# Py_car_2021-03-04.net
KiCad netlist of a schematic drawn in EasyEDA
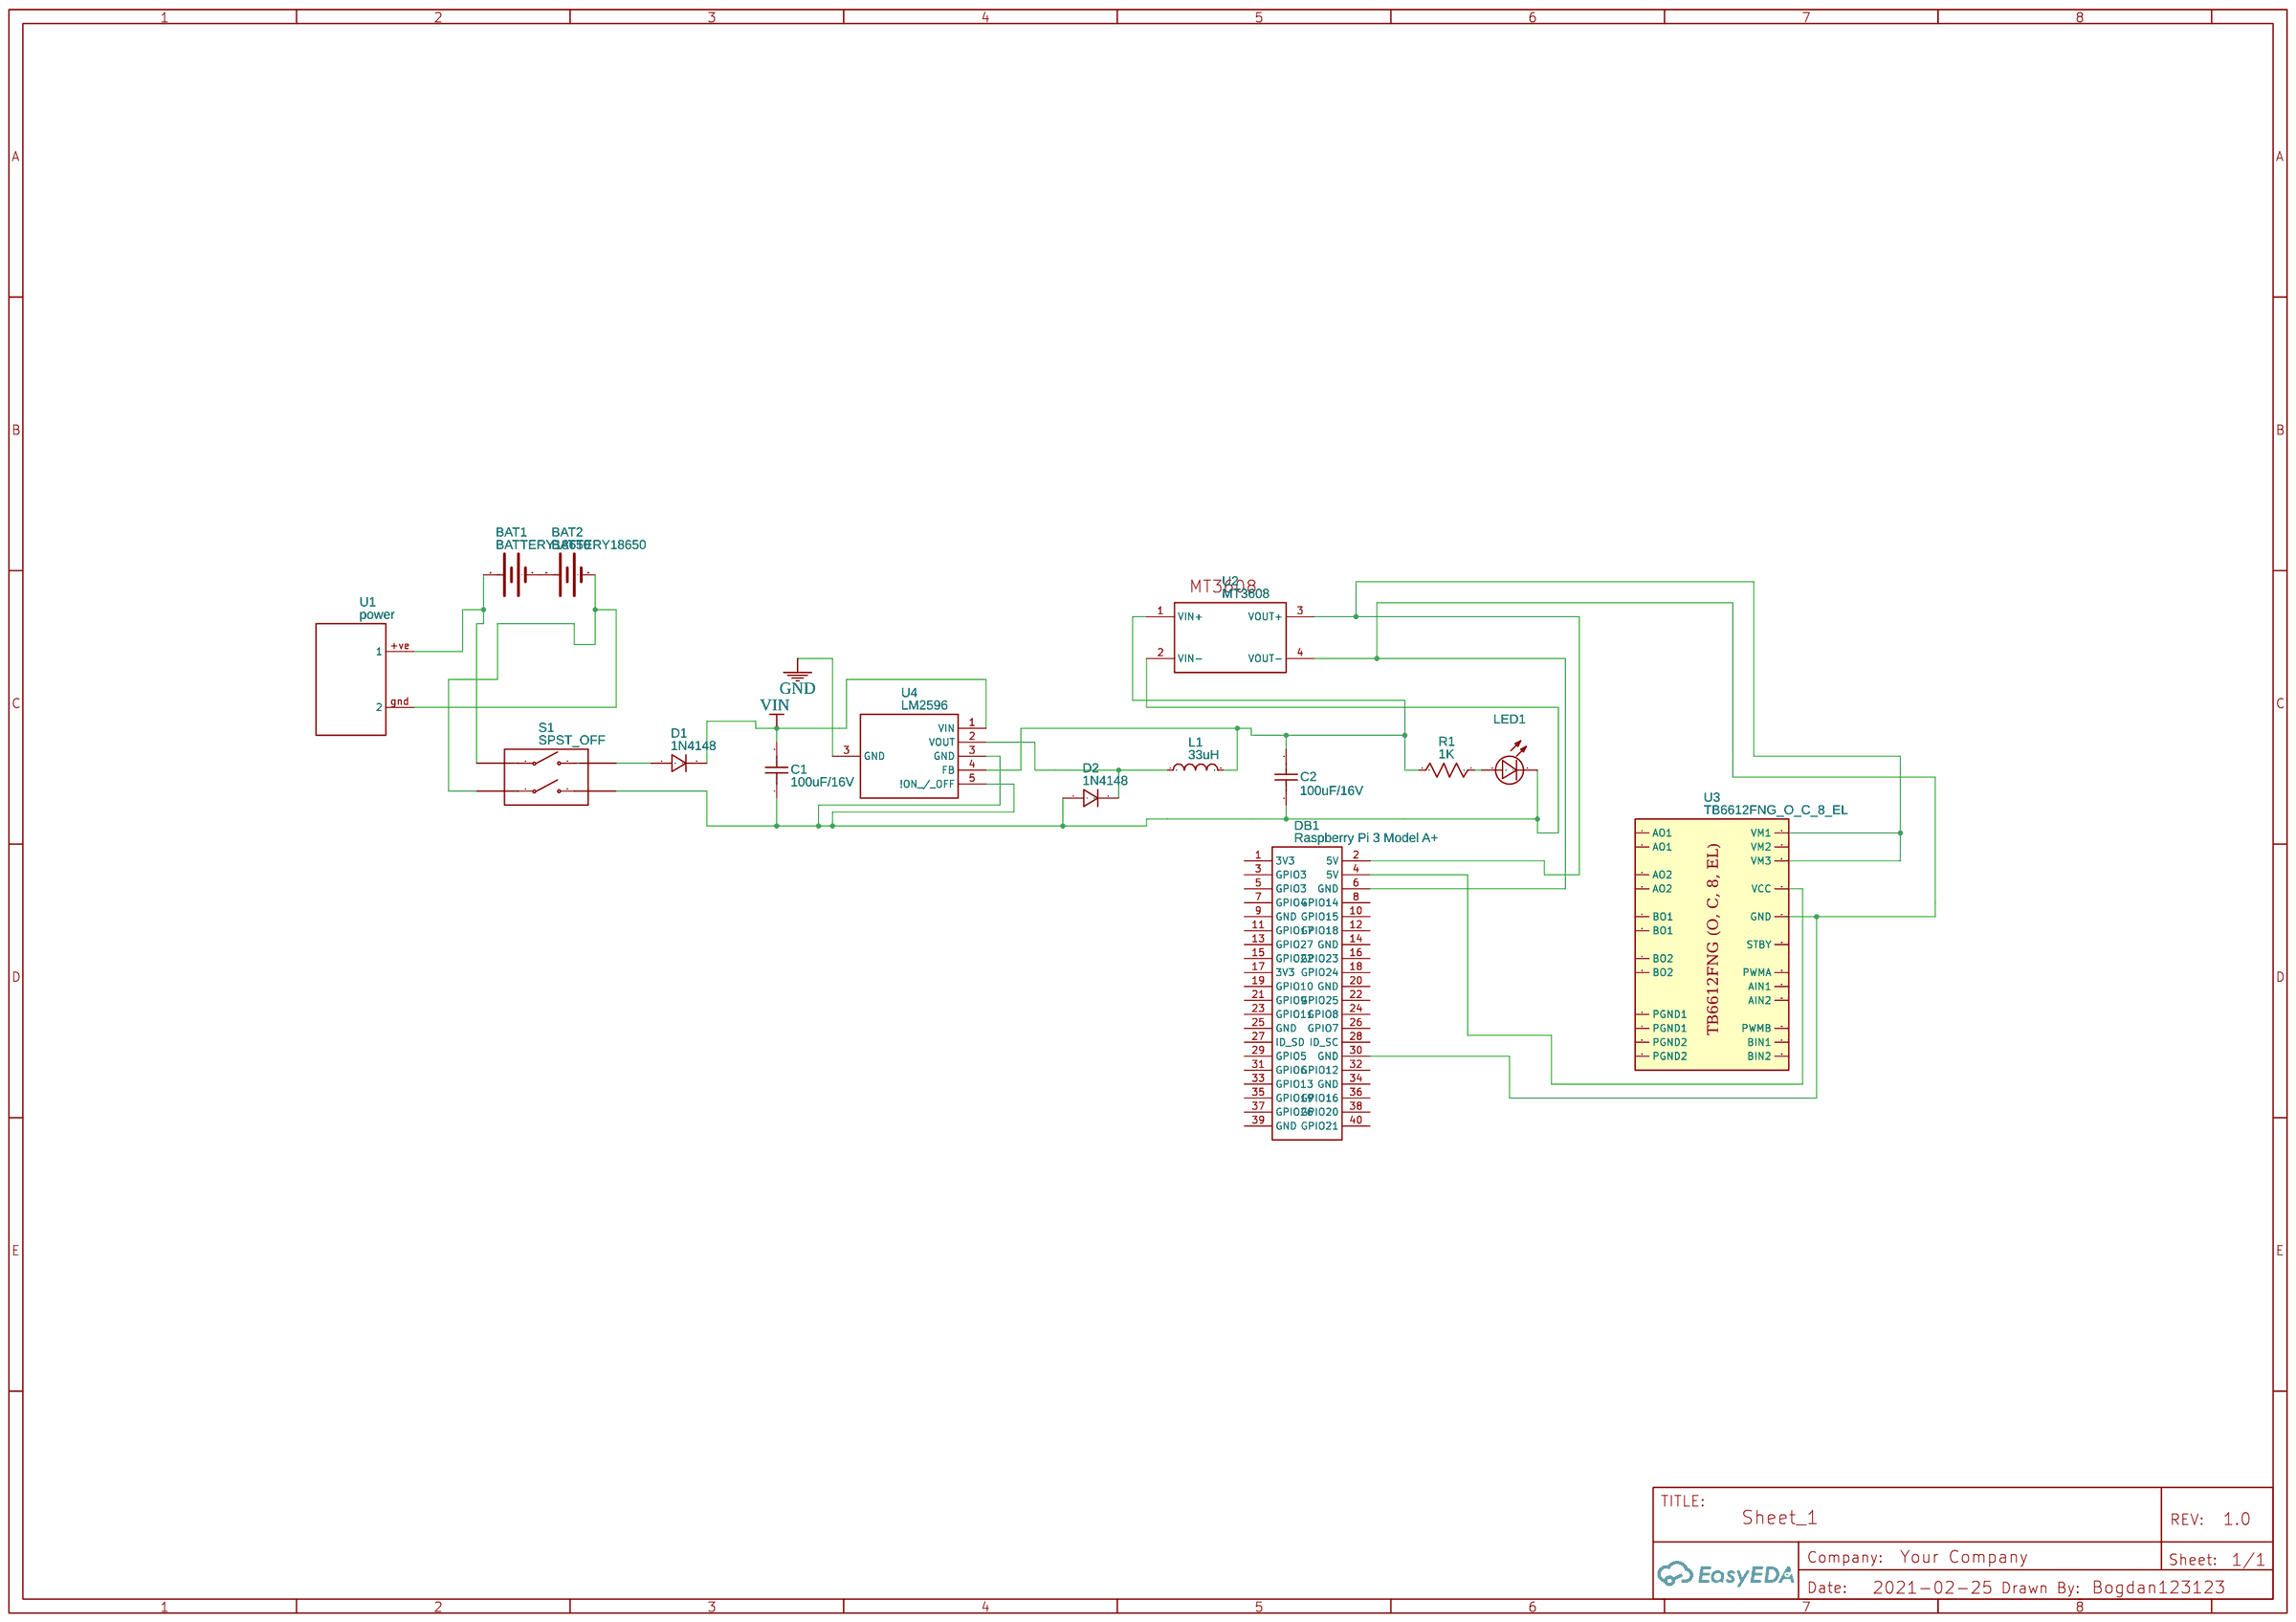
[diagram p0: schematic sheet]

(export (version "E")
  (design (tool "Eeschema 10.0.6"))
  (components
    (comp (ref "BAT1") (value "BATTERY18650") (libsource (lib "") (part "BATTERY18650")))
    (comp (ref "BAT2") (value "BATTERY18650") (libsource (lib "") (part "BATTERY18650")))
    (comp (ref "C1") (value "100uF/16V") (libsource (lib "") (part "Capacitor_US")))
    (comp (ref "C2") (value "100uF/16V") (libsource (lib "") (part "Capacitor_US")))
    (comp (ref "D1") (value "1N4148") (libsource (lib "") (part "1N4148")))
    (comp (ref "D2") (value "1N4148") (libsource (lib "") (part "1N4148")))
    (comp (ref "DB1")
      (value "Raspberry Pi 3 Model A+")
      (fields
        (field (name "BOM_Manufacturer Part") "RPI3-MODAP")
        (field (name "BOM_Supplier Part") "2946269")
      )
      (libsource (lib "") (part "Raspberry Pi 3 Model A+"))
    )
    (comp (ref "L1") (value "33uH") (libsource (lib "") (part "Inductor")))
    (comp (ref "LED1") (value "LED") (libsource (lib "") (part "LED")))
    (comp (ref "R1") (value "1K") (libsource (lib "") (part "Resistor_US")))
    (comp (ref "S1") (value "SPST_OFF") (libsource (lib "") (part "SPST_OFF")))
    (comp (ref "U1") (value "power") (libsource (lib "") (part "power")))
    (comp (ref "U2") (value "MT3608") (libsource (lib "") (part "MT3608")))
    (comp (ref "U3") (value "TB6612FNG_O_C_8_EL") (libsource (lib "") (part "TB6612FNG_O_C_8_EL")))
    (comp (ref "U4") (value "LM2596") (libsource (lib "") (part "LM2596")))
  )
  (nets
    (net (code "1") (name "GND") (class "Default")
      (node (ref "U4") (pin "3") (pinfunction "GND_3") (pintype "unspecified"))
    )
    (net (code "2") (name "Net-(BAT1-+)") (class "Default")
      (node (ref "BAT1") (pin "PWR@1") (pinfunction "+_PWR@1") (pintype "passive"))
      (node (ref "U1") (pin "+ve") (pinfunction "1_+ve") (pintype "unspecified"))
    )
    (net (code "3") (name "Net-(BAT1--)") (class "Default")
      (node (ref "BAT1") (pin "GND@1") (pinfunction "-_GND@1") (pintype "passive"))
      (node (ref "BAT2") (pin "PWR@1") (pinfunction "+_PWR@1") (pintype "passive"))
    )
    (net (code "4") (name "Net-(BAT2--)") (class "Default")
      (node (ref "BAT2") (pin "GND@1") (pinfunction "-_GND@1") (pintype "passive"))
      (node (ref "U1") (pin "gnd") (pinfunction "2_gnd") (pintype "unspecified"))
    )
    (net (code "5") (name "Net-(D2-A)") (class "Default")
      (node (ref "C1") (pin "1") (pinfunction "1_1") (pintype "unspecified"))
      (node (ref "C2") (pin "1") (pinfunction "1_1") (pintype "unspecified"))
      (node (ref "D2") (pin "1") (pinfunction "A_1") (pintype "unspecified"))
      (node (ref "LED1") (pin "2") (pinfunction "-_2") (pintype "unspecified"))
      (node (ref "U2") (pin "2") (pinfunction "VIN-_2") (pintype "unspecified"))
      (node (ref "U4") (pin "3") (pinfunction "GND_3") (pintype "unspecified"))
      (node (ref "U4") (pin "5") (pinfunction "!ON_/_OFF_5") (pintype "unspecified"))
    )
    (net (code "6") (name "Net-(D2-K)") (class "Default")
      (node (ref "D2") (pin "2") (pinfunction "K_2") (pintype "unspecified"))
      (node (ref "L1") (pin "1") (pinfunction "1_1") (pintype "unspecified"))
      (node (ref "U4") (pin "2") (pinfunction "VOUT_2") (pintype "unspecified"))
    )
    (net (code "7") (name "Net-(LED1-+)") (class "Default")
      (node (ref "LED1") (pin "1") (pinfunction "+_1") (pintype "unspecified"))
      (node (ref "R1") (pin "2") (pinfunction "2_2") (pintype "unspecified"))
    )
    (net (code "8") (name "Net-(U2-VIN+)") (class "Default")
      (node (ref "C2") (pin "2") (pinfunction "2_2") (pintype "unspecified"))
      (node (ref "L1") (pin "2") (pinfunction "2_2") (pintype "unspecified"))
      (node (ref "R1") (pin "1") (pinfunction "1_1") (pintype "unspecified"))
      (node (ref "U2") (pin "1") (pinfunction "VIN+_1") (pintype "unspecified"))
      (node (ref "U4") (pin "4") (pinfunction "FB_4") (pintype "unspecified"))
    )
    (net (code "9") (name "Net-(U2-VOUT+)") (class "Default")
      (node (ref "DB1") (pin "2") (pinfunction "5V_2") (pintype "unspecified"))
      (node (ref "U2") (pin "3") (pinfunction "VOUT+_3") (pintype "unspecified"))
      (node (ref "U3") (pin "14") (pinfunction "VM3_14") (pintype "unspecified"))
      (node (ref "U3") (pin "24") (pinfunction "VM1_24") (pintype "unspecified"))
    )
    (net (code "10") (name "Net-(U2-VOUT-)") (class "Default")
      (node (ref "DB1") (pin "30") (pinfunction "GND_30") (pintype "unspecified"))
      (node (ref "DB1") (pin "6") (pinfunction "GND_6") (pintype "unspecified"))
      (node (ref "U2") (pin "4") (pinfunction "VOUT-_4") (pintype "unspecified"))
      (node (ref "U3") (pin "18") (pinfunction "GND_18") (pintype "unspecified"))
    )
    (net (code "11") (name "Net-(U3-VCC)") (class "Default")
      (node (ref "DB1") (pin "4") (pinfunction "5V_4") (pintype "unspecified"))
      (node (ref "U3") (pin "20") (pinfunction "VCC_20") (pintype "unspecified"))
    )
    (net (code "12") (name "VIN") (class "Default")
      (node (ref "C1") (pin "2") (pinfunction "2_2") (pintype "unspecified"))
      (node (ref "D1") (pin "2") (pinfunction "K_2") (pintype "unspecified"))
      (node (ref "U4") (pin "1") (pinfunction "VIN_1") (pintype "unspecified"))
    )
    (net (code "13") (name "unconnected-(D1-A-Pad1)") (class "Default")
      (node (ref "D1") (pin "1") (pinfunction "A_1") (pintype "unspecified"))
    )
    (net (code "14") (name "unconnected-(DB1-3V3-Pad1)") (class "Default")
      (node (ref "DB1") (pin "1") (pinfunction "3V3_1") (pintype "unspecified"))
    )
    (net (code "15") (name "unconnected-(DB1-3V3-Pad17)") (class "Default")
      (node (ref "DB1") (pin "17") (pinfunction "3V3_17") (pintype "unspecified"))
    )
    (net (code "16") (name "unconnected-(DB1-GND-Pad9)") (class "Default")
      (node (ref "DB1") (pin "9") (pinfunction "GND_9") (pintype "unspecified"))
    )
    (net (code "17") (name "unconnected-(DB1-GND-Pad14)") (class "Default")
      (node (ref "DB1") (pin "14") (pinfunction "GND_14") (pintype "unspecified"))
    )
    (net (code "18") (name "unconnected-(DB1-GND-Pad20)") (class "Default")
      (node (ref "DB1") (pin "20") (pinfunction "GND_20") (pintype "unspecified"))
    )
    (net (code "19") (name "unconnected-(DB1-GND-Pad25)") (class "Default")
      (node (ref "DB1") (pin "25") (pinfunction "GND_25") (pintype "unspecified"))
    )
    (net (code "20") (name "unconnected-(DB1-GND-Pad34)") (class "Default")
      (node (ref "DB1") (pin "34") (pinfunction "GND_34") (pintype "unspecified"))
    )
    (net (code "21") (name "unconnected-(DB1-GND-Pad39)") (class "Default")
      (node (ref "DB1") (pin "39") (pinfunction "GND_39") (pintype "unspecified"))
    )
    (net (code "22") (name "unconnected-(DB1-GPIO3-Pad3)") (class "Default")
      (node (ref "DB1") (pin "3") (pinfunction "GPIO3_3") (pintype "bidirectional"))
    )
    (net (code "23") (name "unconnected-(DB1-GPIO3-Pad5)") (class "Default")
      (node (ref "DB1") (pin "5") (pinfunction "GPIO3_5") (pintype "bidirectional"))
    )
    (net (code "24") (name "unconnected-(DB1-GPIO4-Pad7)") (class "Default")
      (node (ref "DB1") (pin "7") (pinfunction "GPIO4_7") (pintype "bidirectional"))
    )
    (net (code "25") (name "unconnected-(DB1-GPIO5-Pad29)") (class "Default")
      (node (ref "DB1") (pin "29") (pinfunction "GPIO5_29") (pintype "bidirectional"))
    )
    (net (code "26") (name "unconnected-(DB1-GPIO6-Pad31)") (class "Default")
      (node (ref "DB1") (pin "31") (pinfunction "GPIO6_31") (pintype "bidirectional"))
    )
    (net (code "27") (name "unconnected-(DB1-GPIO7-Pad26)") (class "Default")
      (node (ref "DB1") (pin "26") (pinfunction "GPIO7_26") (pintype "bidirectional"))
    )
    (net (code "28") (name "unconnected-(DB1-GPIO8-Pad24)") (class "Default")
      (node (ref "DB1") (pin "24") (pinfunction "GPIO8_24") (pintype "bidirectional"))
    )
    (net (code "29") (name "unconnected-(DB1-GPIO9-Pad21)") (class "Default")
      (node (ref "DB1") (pin "21") (pinfunction "GPIO9_21") (pintype "bidirectional"))
    )
    (net (code "30") (name "unconnected-(DB1-GPIO10-Pad19)") (class "Default")
      (node (ref "DB1") (pin "19") (pinfunction "GPIO10_19") (pintype "bidirectional"))
    )
    (net (code "31") (name "unconnected-(DB1-GPIO11-Pad23)") (class "Default")
      (node (ref "DB1") (pin "23") (pinfunction "GPIO11_23") (pintype "bidirectional"))
    )
    (net (code "32") (name "unconnected-(DB1-GPIO12-Pad32)") (class "Default")
      (node (ref "DB1") (pin "32") (pinfunction "GPIO12_32") (pintype "bidirectional"))
    )
    (net (code "33") (name "unconnected-(DB1-GPIO13-Pad33)") (class "Default")
      (node (ref "DB1") (pin "33") (pinfunction "GPIO13_33") (pintype "bidirectional"))
    )
    (net (code "34") (name "unconnected-(DB1-GPIO14-Pad8)") (class "Default")
      (node (ref "DB1") (pin "8") (pinfunction "GPIO14_8") (pintype "bidirectional"))
    )
    (net (code "35") (name "unconnected-(DB1-GPIO15-Pad10)") (class "Default")
      (node (ref "DB1") (pin "10") (pinfunction "GPIO15_10") (pintype "bidirectional"))
    )
    (net (code "36") (name "unconnected-(DB1-GPIO16-Pad36)") (class "Default")
      (node (ref "DB1") (pin "36") (pinfunction "GPIO16_36") (pintype "bidirectional"))
    )
    (net (code "37") (name "unconnected-(DB1-GPIO17-Pad11)") (class "Default")
      (node (ref "DB1") (pin "11") (pinfunction "GPIO17_11") (pintype "bidirectional"))
    )
    (net (code "38") (name "unconnected-(DB1-GPIO18-Pad12)") (class "Default")
      (node (ref "DB1") (pin "12") (pinfunction "GPIO18_12") (pintype "bidirectional"))
    )
    (net (code "39") (name "unconnected-(DB1-GPIO19-Pad35)") (class "Default")
      (node (ref "DB1") (pin "35") (pinfunction "GPIO19_35") (pintype "bidirectional"))
    )
    (net (code "40") (name "unconnected-(DB1-GPIO20-Pad38)") (class "Default")
      (node (ref "DB1") (pin "38") (pinfunction "GPIO20_38") (pintype "bidirectional"))
    )
    (net (code "41") (name "unconnected-(DB1-GPIO21-Pad40)") (class "Default")
      (node (ref "DB1") (pin "40") (pinfunction "GPIO21_40") (pintype "bidirectional"))
    )
    (net (code "42") (name "unconnected-(DB1-GPIO22-Pad15)") (class "Default")
      (node (ref "DB1") (pin "15") (pinfunction "GPIO22_15") (pintype "bidirectional"))
    )
    (net (code "43") (name "unconnected-(DB1-GPIO23-Pad16)") (class "Default")
      (node (ref "DB1") (pin "16") (pinfunction "GPIO23_16") (pintype "bidirectional"))
    )
    (net (code "44") (name "unconnected-(DB1-GPIO24-Pad18)") (class "Default")
      (node (ref "DB1") (pin "18") (pinfunction "GPIO24_18") (pintype "bidirectional"))
    )
    (net (code "45") (name "unconnected-(DB1-GPIO25-Pad22)") (class "Default")
      (node (ref "DB1") (pin "22") (pinfunction "GPIO25_22") (pintype "bidirectional"))
    )
    (net (code "46") (name "unconnected-(DB1-GPIO26-Pad37)") (class "Default")
      (node (ref "DB1") (pin "37") (pinfunction "GPIO26_37") (pintype "bidirectional"))
    )
    (net (code "47") (name "unconnected-(DB1-GPIO27-Pad13)") (class "Default")
      (node (ref "DB1") (pin "13") (pinfunction "GPIO27_13") (pintype "bidirectional"))
    )
    (net (code "48") (name "unconnected-(DB1-ID_SC-Pad28)") (class "Default")
      (node (ref "DB1") (pin "28") (pinfunction "ID_SC_28") (pintype "unspecified"))
    )
    (net (code "49") (name "unconnected-(DB1-ID_SD-Pad27)") (class "Default")
      (node (ref "DB1") (pin "27") (pinfunction "ID_SD_27") (pintype "unspecified"))
    )
    (net (code "50") (name "unconnected-(S1-Pad1_)") (class "Default")
      (node (ref "S1") (pin "1_") (pinfunction "1__1_") (pintype "unspecified"))
    )
    (net (code "51") (name "unconnected-(S1-Pad1_)_1") (class "Default")
      (node (ref "S1") (pin "1_") (pinfunction "1__1_") (pintype "unspecified"))
    )
    (net (code "52") (name "unconnected-(S1-Pad2_)") (class "Default")
      (node (ref "S1") (pin "2_") (pinfunction "2__2_") (pintype "unspecified"))
    )
    (net (code "53") (name "unconnected-(S1-Pad2_)_1") (class "Default")
      (node (ref "S1") (pin "2_") (pinfunction "2__2_") (pintype "unspecified"))
    )
    (net (code "54") (name "unconnected-(U3-AIN1-Pad21)") (class "Default")
      (node (ref "U3") (pin "21") (pinfunction "AIN1_21") (pintype "unspecified"))
    )
    (net (code "55") (name "unconnected-(U3-AIN2-Pad22)") (class "Default")
      (node (ref "U3") (pin "22") (pinfunction "AIN2_22") (pintype "unspecified"))
    )
    (net (code "56") (name "unconnected-(U3-AO1-Pad1)") (class "Default")
      (node (ref "U3") (pin "1") (pinfunction "AO1_1") (pintype "unspecified"))
    )
    (net (code "57") (name "unconnected-(U3-AO1-Pad2)") (class "Default")
      (node (ref "U3") (pin "2") (pinfunction "AO1_2") (pintype "unspecified"))
    )
    (net (code "58") (name "unconnected-(U3-AO2-Pad5)") (class "Default")
      (node (ref "U3") (pin "5") (pinfunction "AO2_5") (pintype "unspecified"))
    )
    (net (code "59") (name "unconnected-(U3-AO2-Pad6)") (class "Default")
      (node (ref "U3") (pin "6") (pinfunction "AO2_6") (pintype "unspecified"))
    )
    (net (code "60") (name "unconnected-(U3-BIN1-Pad17)") (class "Default")
      (node (ref "U3") (pin "17") (pinfunction "BIN1_17") (pintype "unspecified"))
    )
    (net (code "61") (name "unconnected-(U3-BIN2-Pad16)") (class "Default")
      (node (ref "U3") (pin "16") (pinfunction "BIN2_16") (pintype "unspecified"))
    )
    (net (code "62") (name "unconnected-(U3-BO1-Pad11)") (class "Default")
      (node (ref "U3") (pin "11") (pinfunction "BO1_11") (pintype "unspecified"))
    )
    (net (code "63") (name "unconnected-(U3-BO1-Pad12)") (class "Default")
      (node (ref "U3") (pin "12") (pinfunction "BO1_12") (pintype "unspecified"))
    )
    (net (code "64") (name "unconnected-(U3-BO2-Pad7)") (class "Default")
      (node (ref "U3") (pin "7") (pinfunction "BO2_7") (pintype "unspecified"))
    )
    (net (code "65") (name "unconnected-(U3-BO2-Pad8)") (class "Default")
      (node (ref "U3") (pin "8") (pinfunction "BO2_8") (pintype "unspecified"))
    )
    (net (code "66") (name "unconnected-(U3-PGND1-Pad3)") (class "Default")
      (node (ref "U3") (pin "3") (pinfunction "PGND1_3") (pintype "unspecified"))
    )
    (net (code "67") (name "unconnected-(U3-PGND1-Pad4)") (class "Default")
      (node (ref "U3") (pin "4") (pinfunction "PGND1_4") (pintype "unspecified"))
    )
    (net (code "68") (name "unconnected-(U3-PGND2-Pad9)") (class "Default")
      (node (ref "U3") (pin "9") (pinfunction "PGND2_9") (pintype "unspecified"))
    )
    (net (code "69") (name "unconnected-(U3-PGND2-Pad10)") (class "Default")
      (node (ref "U3") (pin "10") (pinfunction "PGND2_10") (pintype "unspecified"))
    )
    (net (code "70") (name "unconnected-(U3-PWMA-Pad23)") (class "Default")
      (node (ref "U3") (pin "23") (pinfunction "PWMA_23") (pintype "unspecified"))
    )
    (net (code "71") (name "unconnected-(U3-PWMB-Pad15)") (class "Default")
      (node (ref "U3") (pin "15") (pinfunction "PWMB_15") (pintype "unspecified"))
    )
    (net (code "72") (name "unconnected-(U3-STBY-Pad19)") (class "Default")
      (node (ref "U3") (pin "19") (pinfunction "STBY_19") (pintype "unspecified"))
    )
    (net (code "73") (name "unconnected-(U3-VM2-Pad13)") (class "Default")
      (node (ref "U3") (pin "13") (pinfunction "VM2_13") (pintype "unspecified"))
    )
  )
)
